# tweeq-MITO.net
KiCad netlist of a schematic drawn in EAGLE
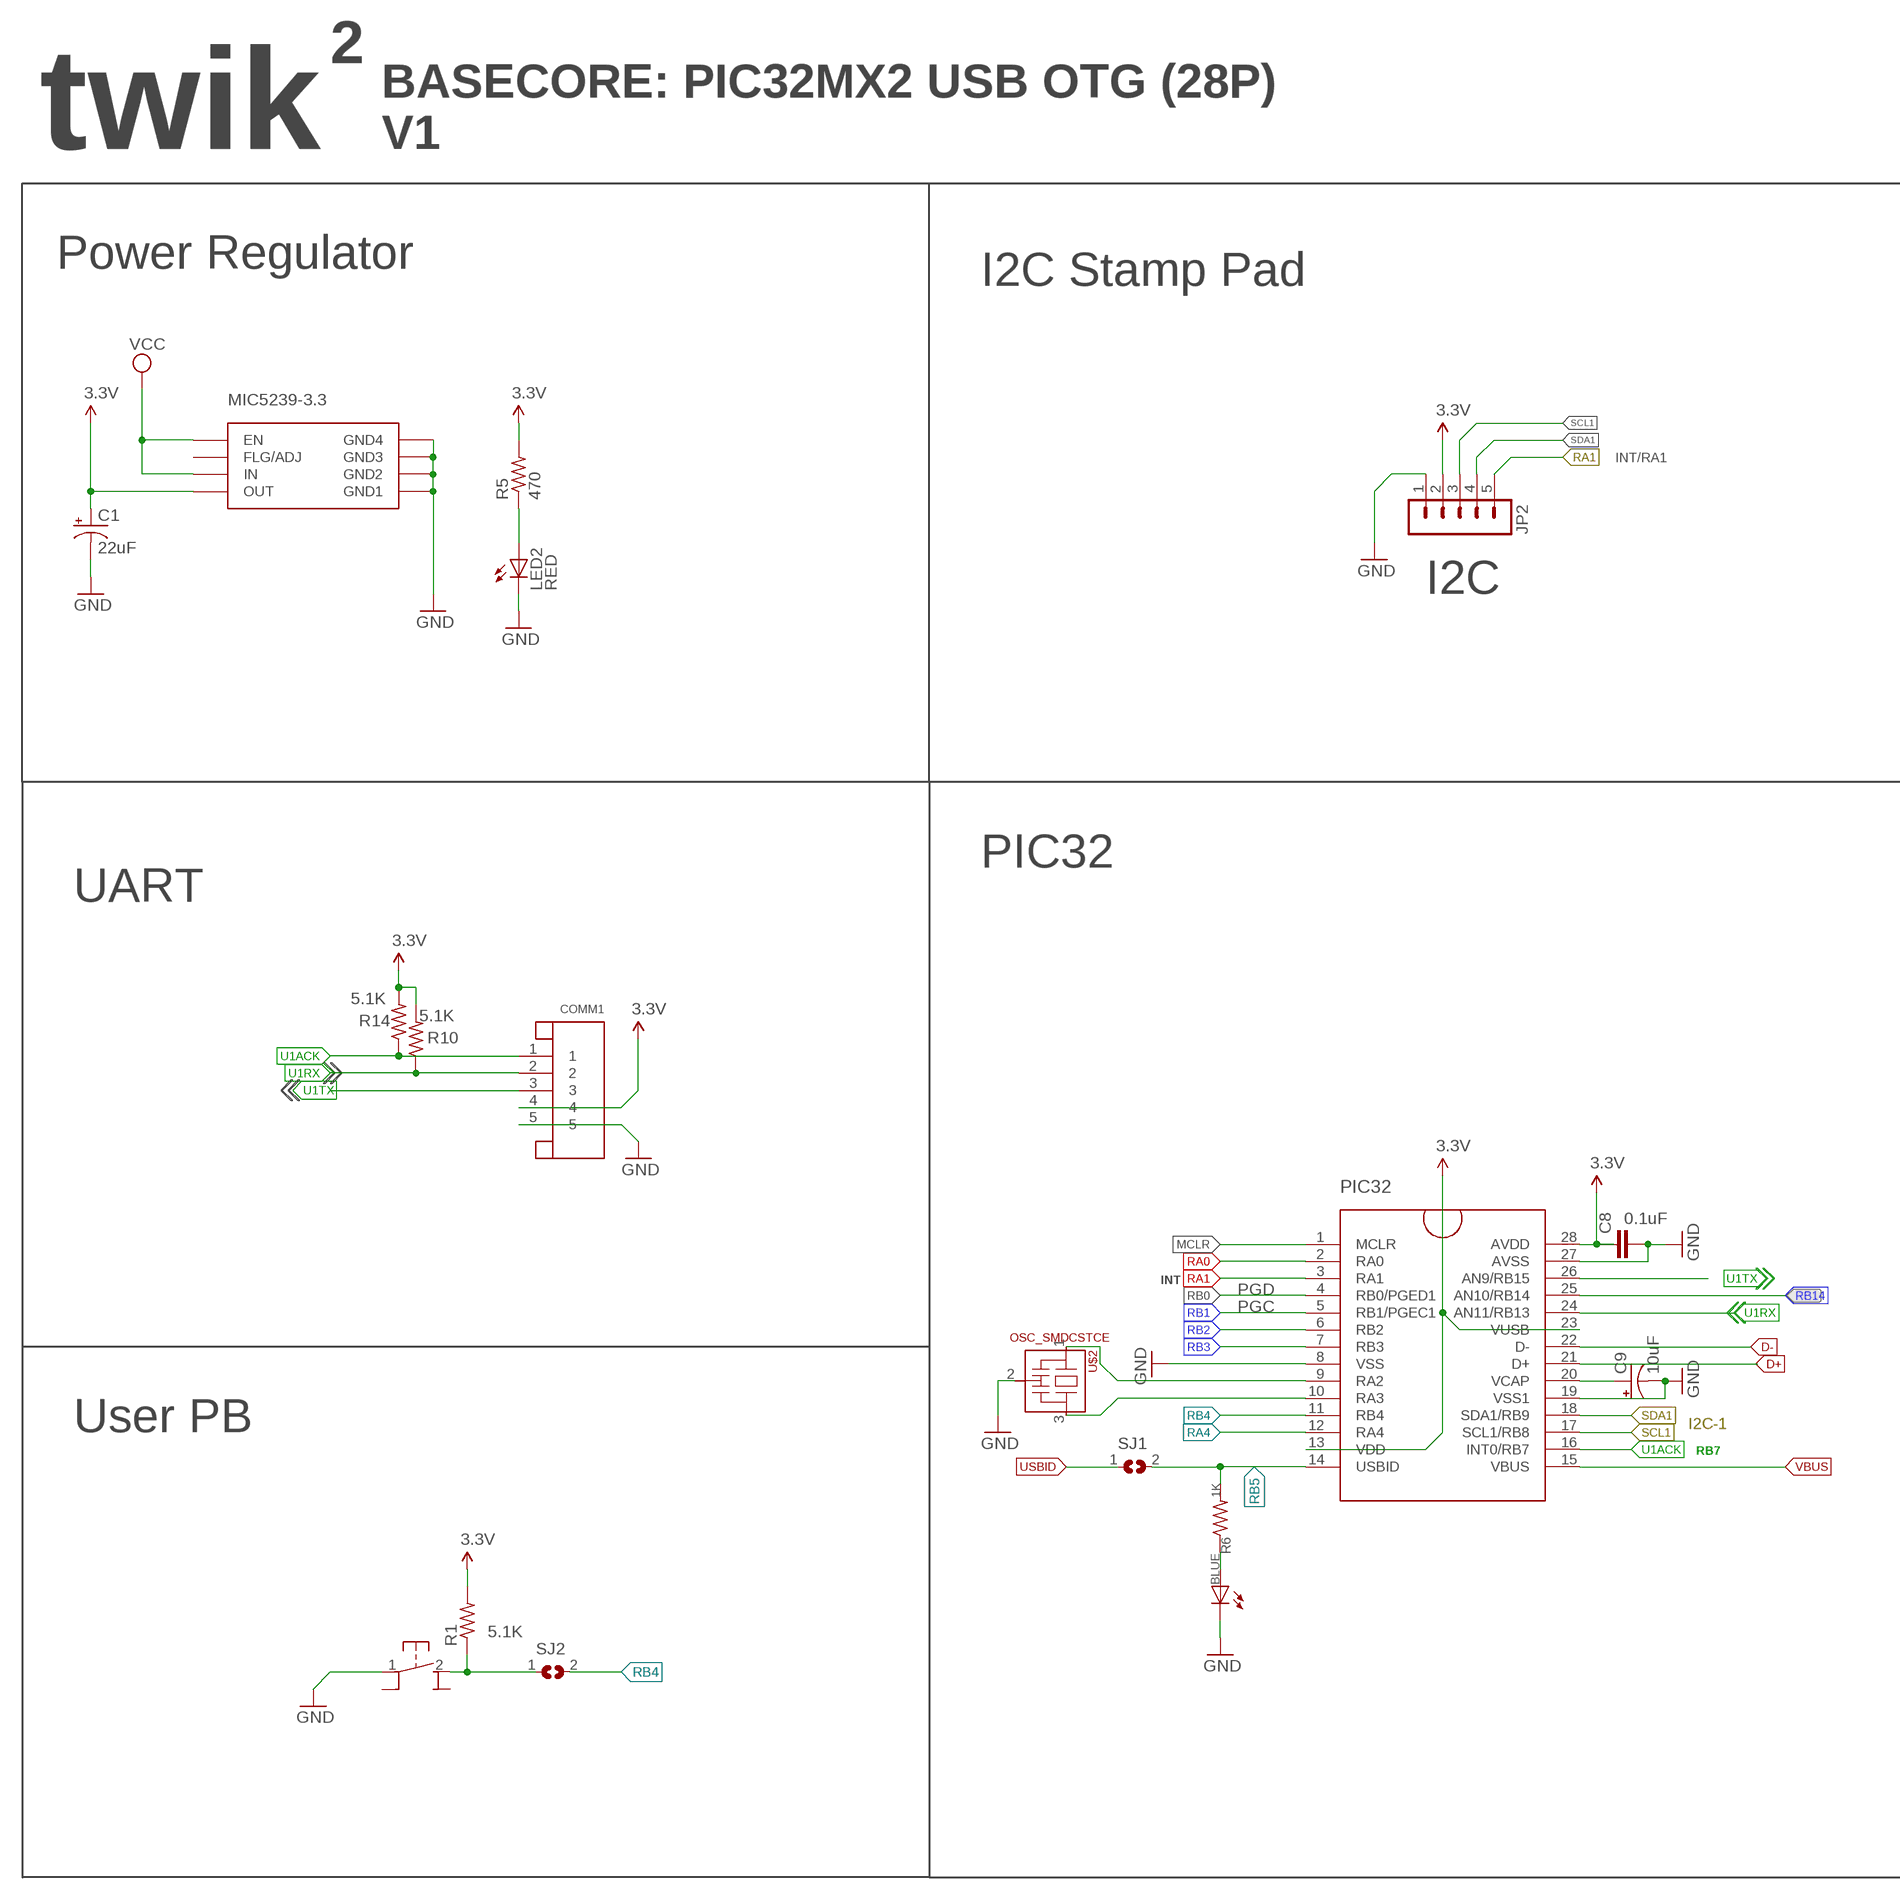
[diagram p0: schematic, sheet 1, part 1 of 2]
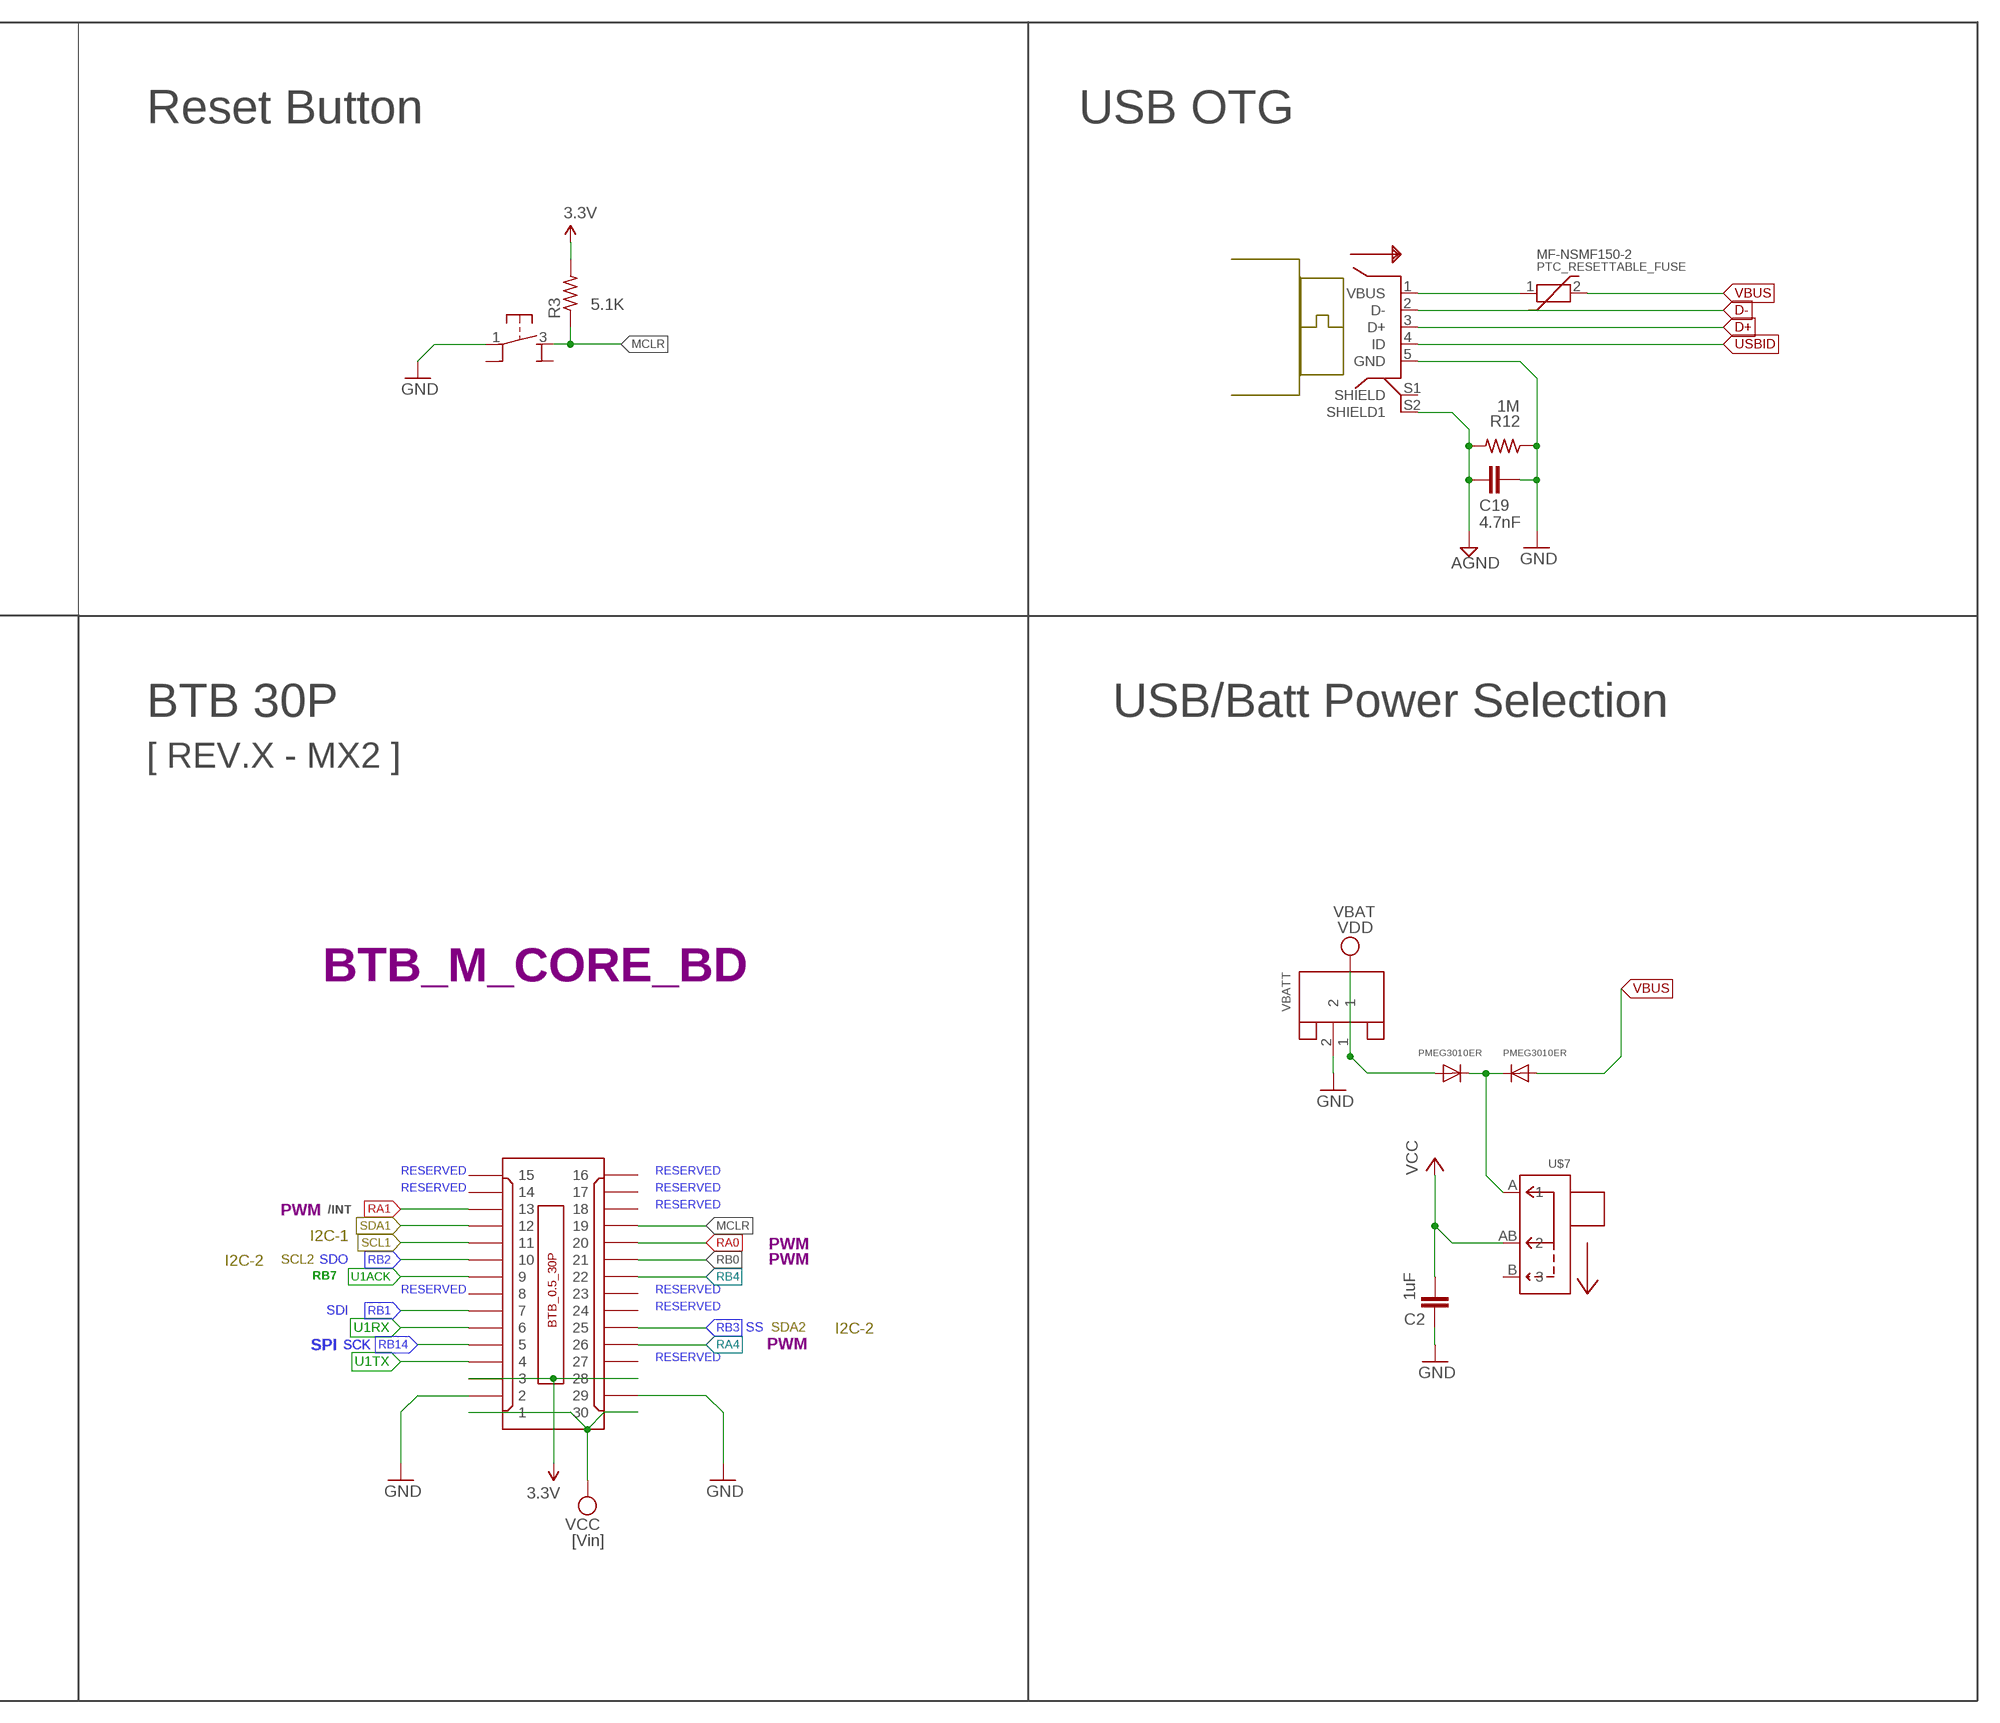
[diagram p1: schematic, sheet 1, part 2 of 2]

(export (version "E")
  (design (tool "Eeschema 10.0.6"))
  (components
    (comp (ref "C1")
      (value "22uF")
      (footprint "eagle-import:SMC_B")
      (libsource (lib "eagle-import") (part "CPOL-USSMCB"))
    )
    (comp (ref "C2")
      (value "1uF")
      (footprint "eagle-import:C0603K")
      (libsource (lib "eagle-import") (part "C-EUC0603K"))
    )
    (comp (ref "C8")
      (value "0.1uF")
      (footprint "eagle-import:C0402K")
      (libsource (lib "eagle-import") (part "C-EUC0402K"))
    )
    (comp (ref "C9")
      (value "10uF")
      (footprint "eagle-import:A_3216-18R")
      (libsource (lib "eagle-import") (part "CPOL-USA/3216-18R"))
    )
    (comp (ref "C19")
      (value "4.7nF")
      (footprint "eagle-import:C0402K")
      (libsource (lib "eagle-import") (part "C-EUC0402K"))
    )
    (comp (ref "COMM1")
      (value "JST-5PINSH")
      (footprint "eagle-import:SH1.0-5PIN")
      (libsource (lib "eagle-import") (part "JST-5PINSH"))
    )
    (comp (ref "JP2")
      (value "M05-11.5MM-SMT")
      (footprint "eagle-import:1X05-1.5MM-SMT")
      (libsource (lib "eagle-import") (part "M05-11.5MM-SMT"))
    )
    (comp (ref "LED2")
      (value "RED")
      (footprint "eagle-import:CHIP-LED0603")
      (libsource (lib "eagle-import") (part "LEDCHIP-LED0603"))
    )
    (comp (ref "MIC5239-3.3")
      (value "MIC5239-MM")
      (footprint "eagle-import:MSOP8")
      (libsource (lib "eagle-import") (part "MIC5239-MM"))
    )
    (comp (ref "PIC32")
      (value "PIC32MX2_B")
      (footprint "eagle-import:SSOP28")
      (libsource (lib "eagle-import") (part "PIC32MX2_B"))
    )
    (comp (ref "PIC_LED")
      (value "BLUE")
      (footprint "eagle-import:CHIP-LED0603")
      (libsource (lib "eagle-import") (part "LEDCHIP-LED0603"))
    )
    (comp (ref "PTC_RESETTABLE_FUSE")
      (value "PTC_FUSE/MF-NSMF150-2")
      (footprint "eagle-import:1206F")
      (libsource (lib "eagle-import") (part "PTC_FUSE/MF-NSMF150-2"))
    )
    (comp (ref "R1")
      (value "5.1K")
      (footprint "eagle-import:R0402")
      (libsource (lib "eagle-import") (part "R-US_R0402"))
    )
    (comp (ref "R3")
      (value "5.1K")
      (footprint "eagle-import:R0402")
      (libsource (lib "eagle-import") (part "R-US_R0402"))
    )
    (comp (ref "R5")
      (value "470")
      (footprint "eagle-import:R0402")
      (libsource (lib "eagle-import") (part "R-US_R0402"))
    )
    (comp (ref "R6")
      (value "1K")
      (footprint "eagle-import:R0402")
      (libsource (lib "eagle-import") (part "R-US_R0402"))
    )
    (comp (ref "R10")
      (value "5.1K")
      (footprint "eagle-import:R0402")
      (libsource (lib "eagle-import") (part "R-US_R0402"))
    )
    (comp (ref "R12")
      (value "1M")
      (footprint "eagle-import:R0402")
      (libsource (lib "eagle-import") (part "R-US_R0402"))
    )
    (comp (ref "R14")
      (value "5.1K")
      (footprint "eagle-import:R0402")
      (libsource (lib "eagle-import") (part "R-US_R0402"))
    )
    (comp (ref "SJ1")
      (value "JUMPER_SJ")
      (footprint "eagle-import:JUMPER_SJ")
      (libsource (lib "eagle-import") (part "JUMPER_SJ"))
    )
    (comp (ref "SJ2")
      (value "JUMPER_SJ")
      (footprint "eagle-import:JUMPER_SJ")
      (libsource (lib "eagle-import") (part "JUMPER_SJ"))
    )
    (comp (ref "U$1")
      (value "BTB_CONN_30P/M")
      (footprint "eagle-import:BTB0.5-30M-3.0G")
      (libsource (lib "eagle-import") (part "BTB_CONN_30P/M"))
    )
    (comp (ref "U$2")
      (value "OSC_SMDCSTCE")
      (footprint "eagle-import:CSTCE_RESONATOR_SMD")
      (libsource (lib "eagle-import") (part "OSC_SMDCSTCE"))
    )
    (comp (ref "U$3")
      (value "PB_MICRO_SMTRIGHTANGLE")
      (footprint "eagle-import:PB_SMT_90D6.2X4.6")
      (libsource (lib "eagle-import") (part "PB_MICRO_SMTRIGHTANGLE"))
    )
    (comp (ref "U$4")
      (value "PB_MICRO_SMT")
      (footprint "eagle-import:PB_SMT_3.5X3X2")
      (libsource (lib "eagle-import") (part "PB_MICRO_SMT"))
    )
    (comp (ref "U$7")
      (value "SLIDE_SWITCH_MINI/MSK1101")
      (footprint "eagle-import:MSK1101")
      (libsource (lib "eagle-import") (part "SLIDE_SWITCH_MINI/MSK1101"))
    )
    (comp (ref "U$9")
      (value "PMEG3010ER/MOD")
      (footprint "eagle-import:SOD123-MOD")
      (libsource (lib "eagle-import") (part "PMEG3010ER/MOD"))
    )
    (comp (ref "U$10")
      (value "PMEG3010ER/MOD")
      (footprint "eagle-import:SOD123-MOD")
      (libsource (lib "eagle-import") (part "PMEG3010ER/MOD"))
    )
    (comp (ref "U$12")
      (value "USB/MICRO-5PF-B")
      (footprint "eagle-import:MICRO_USB_5PF_B")
      (libsource (lib "eagle-import") (part "USB/MICRO-5PF-B"))
    )
    (comp (ref "VBATT")
      (value "JST-2PINSH")
      (footprint "eagle-import:SH1.0-2PIN")
      (libsource (lib "eagle-import") (part "JST-2PINSH"))
    )
  )
  (nets
    (net (code "1") (name "3.3V") (class "Default")
      (node (ref "C1") (pin "+") (pinfunction "+_+") (pintype "passive"))
      (node (ref "C8") (pin "1") (pinfunction "1_1") (pintype "passive"))
      (node (ref "COMM1") (pin "4") (pinfunction "4_4") (pintype "bidirectional"))
      (node (ref "JP2") (pin "2") (pinfunction "2_2") (pintype "passive"))
      (node (ref "MIC5239-3.3") (pin "4") (pinfunction "OUT_4") (pintype "bidirectional"))
      (node (ref "PIC32") (pin "13") (pinfunction "VDD_13") (pintype "bidirectional"))
      (node (ref "PIC32") (pin "23") (pinfunction "VUSB_23") (pintype "bidirectional"))
      (node (ref "PIC32") (pin "28") (pinfunction "AVDD_28") (pintype "bidirectional"))
      (node (ref "R1") (pin "2") (pinfunction "2_2") (pintype "passive"))
      (node (ref "R10") (pin "2") (pinfunction "2_2") (pintype "passive"))
      (node (ref "R14") (pin "2") (pinfunction "2_2") (pintype "passive"))
      (node (ref "R3") (pin "2") (pinfunction "2_2") (pintype "passive"))
      (node (ref "R5") (pin "2") (pinfunction "2_2") (pintype "passive"))
      (node (ref "U$1") (pin "28") (pinfunction "28_28") (pintype "bidirectional"))
      (node (ref "U$1") (pin "3") (pinfunction "3_3") (pintype "bidirectional"))
    )
    (net (code "2") (name "AGND") (class "Default")
      (node (ref "C19") (pin "2") (pinfunction "2_2") (pintype "passive"))
      (node (ref "R12") (pin "2") (pinfunction "2_2") (pintype "passive"))
      (node (ref "U$12") (pin "S2") (pinfunction "SHIELD1_S2") (pintype "bidirectional"))
    )
    (net (code "3") (name "D+") (class "Default")
      (node (ref "PIC32") (pin "21") (pinfunction "D+_21") (pintype "bidirectional"))
      (node (ref "U$12") (pin "3") (pinfunction "D+_3") (pintype "bidirectional"))
    )
    (net (code "4") (name "D-") (class "Default")
      (node (ref "PIC32") (pin "22") (pinfunction "D-_22") (pintype "bidirectional"))
      (node (ref "U$12") (pin "2") (pinfunction "D-_2") (pintype "bidirectional"))
    )
    (net (code "5") (name "GND") (class "Default")
      (node (ref "C1") (pin "-") (pinfunction "-_-") (pintype "passive"))
      (node (ref "C19") (pin "1") (pinfunction "1_1") (pintype "passive"))
      (node (ref "C2") (pin "1") (pinfunction "1_1") (pintype "passive"))
      (node (ref "C8") (pin "2") (pinfunction "2_2") (pintype "passive"))
      (node (ref "C9") (pin "-") (pinfunction "-_-") (pintype "passive"))
      (node (ref "COMM1") (pin "5") (pinfunction "5_5") (pintype "bidirectional"))
      (node (ref "JP2") (pin "1") (pinfunction "1_1") (pintype "passive"))
      (node (ref "LED2") (pin "C") (pinfunction "C_C") (pintype "passive"))
      (node (ref "MIC5239-3.3") (pin "5") (pinfunction "GND1_5") (pintype "bidirectional"))
      (node (ref "MIC5239-3.3") (pin "6") (pinfunction "GND2_6") (pintype "bidirectional"))
      (node (ref "MIC5239-3.3") (pin "7") (pinfunction "GND3_7") (pintype "bidirectional"))
      (node (ref "MIC5239-3.3") (pin "8") (pinfunction "GND4_8") (pintype "bidirectional"))
      (node (ref "PIC32") (pin "19") (pinfunction "VSS1_19") (pintype "bidirectional"))
      (node (ref "PIC32") (pin "27") (pinfunction "AVSS_27") (pintype "bidirectional"))
      (node (ref "PIC32") (pin "8") (pinfunction "VSS_8") (pintype "bidirectional"))
      (node (ref "PIC_LED") (pin "C") (pinfunction "C_C") (pintype "passive"))
      (node (ref "R12") (pin "1") (pinfunction "1_1") (pintype "passive"))
      (node (ref "U$1") (pin "2") (pinfunction "2_2") (pintype "bidirectional"))
      (node (ref "U$1") (pin "29") (pinfunction "29_29") (pintype "bidirectional"))
      (node (ref "U$12") (pin "5") (pinfunction "GND_5") (pintype "bidirectional"))
      (node (ref "U$2") (pin "2") (pinfunction "VSS_2") (pintype "power_in"))
      (node (ref "U$3") (pin "1") (pinfunction "1_1") (pintype "passive"))
      (node (ref "U$4") (pin "1") (pinfunction "1_1") (pintype "passive"))
      (node (ref "VBATT") (pin "2") (pinfunction "2_2") (pintype "bidirectional"))
    )
    (net (code "6") (name "MCLR") (class "Default")
      (node (ref "PIC32") (pin "1") (pinfunction "MCLR_1") (pintype "bidirectional"))
      (node (ref "R3") (pin "1") (pinfunction "1_1") (pintype "passive"))
      (node (ref "U$1") (pin "19") (pinfunction "19_19") (pintype "bidirectional"))
      (node (ref "U$4") (pin "3") (pinfunction "2_3") (pintype "passive"))
    )
    (net (code "7") (name "Net-(LED2-PadA)") (class "Default")
      (node (ref "LED2") (pin "A") (pinfunction "A_A") (pintype "passive"))
      (node (ref "R5") (pin "1") (pinfunction "1_1") (pintype "passive"))
    )
    (net (code "8") (name "Net-(PIC32-RA2)") (class "Default")
      (node (ref "PIC32") (pin "9") (pinfunction "RA2_9") (pintype "bidirectional"))
      (node (ref "U$2") (pin "1") (pinfunction "1_1") (pintype "output"))
    )
    (net (code "9") (name "Net-(PIC32-RA3)") (class "Default")
      (node (ref "PIC32") (pin "10") (pinfunction "RA3_10") (pintype "bidirectional"))
      (node (ref "U$2") (pin "3") (pinfunction "3_3") (pintype "input"))
    )
    (net (code "10") (name "Net-(PIC32-VCAP)") (class "Default")
      (node (ref "C9") (pin "+") (pinfunction "+_+") (pintype "passive"))
      (node (ref "PIC32") (pin "20") (pinfunction "VCAP_20") (pintype "bidirectional"))
    )
    (net (code "11") (name "Net-(PIC_LED-PadA)") (class "Default")
      (node (ref "PIC_LED") (pin "A") (pinfunction "A_A") (pintype "passive"))
      (node (ref "R6") (pin "1") (pinfunction "1_1") (pintype "passive"))
    )
    (net (code "12") (name "Net-(R1-Pad1)") (class "Default")
      (node (ref "R1") (pin "1") (pinfunction "1_1") (pintype "passive"))
      (node (ref "SJ2") (pin "1") (pinfunction "1_1") (pintype "passive"))
      (node (ref "U$3") (pin "2") (pinfunction "2_2") (pintype "passive"))
    )
    (net (code "13") (name "Net-(U$7-1)") (class "Default")
      (node (ref "U$10") (pin "C") (pinfunction "C_C") (pintype "passive"))
      (node (ref "U$7") (pin "A") (pinfunction "1_A") (pintype "bidirectional"))
      (node (ref "U$9") (pin "C") (pinfunction "C_C") (pintype "passive"))
    )
    (net (code "14") (name "Net-(U$12-VBUS)") (class "Default")
      (node (ref "PTC_RESETTABLE_FUSE") (pin "1") (pinfunction "1_1") (pintype "bidirectional"))
      (node (ref "U$12") (pin "1") (pinfunction "VBUS_1") (pintype "bidirectional"))
    )
    (net (code "15") (name "RA0") (class "Default")
      (node (ref "PIC32") (pin "2") (pinfunction "RA0_2") (pintype "bidirectional"))
      (node (ref "U$1") (pin "20") (pinfunction "20_20") (pintype "bidirectional"))
    )
    (net (code "16") (name "RA1") (class "Default")
      (node (ref "JP2") (pin "5") (pinfunction "5_5") (pintype "passive"))
      (node (ref "PIC32") (pin "3") (pinfunction "RA1_3") (pintype "bidirectional"))
      (node (ref "U$1") (pin "13") (pinfunction "13_13") (pintype "bidirectional"))
    )
    (net (code "17") (name "RA4") (class "Default")
      (node (ref "PIC32") (pin "12") (pinfunction "RA4_12") (pintype "bidirectional"))
      (node (ref "U$1") (pin "26") (pinfunction "26_26") (pintype "bidirectional"))
    )
    (net (code "18") (name "RB0") (class "Default")
      (node (ref "PIC32") (pin "4") (pinfunction "RB0/PGED1_4") (pintype "bidirectional"))
      (node (ref "U$1") (pin "21") (pinfunction "21_21") (pintype "bidirectional"))
    )
    (net (code "19") (name "RB1") (class "Default")
      (node (ref "PIC32") (pin "5") (pinfunction "RB1/PGEC1_5") (pintype "bidirectional"))
      (node (ref "U$1") (pin "7") (pinfunction "7_7") (pintype "bidirectional"))
    )
    (net (code "20") (name "RB2") (class "Default")
      (node (ref "PIC32") (pin "6") (pinfunction "RB2_6") (pintype "bidirectional"))
      (node (ref "U$1") (pin "10") (pinfunction "10_10") (pintype "bidirectional"))
    )
    (net (code "21") (name "RB3") (class "Default")
      (node (ref "PIC32") (pin "7") (pinfunction "RB3_7") (pintype "bidirectional"))
      (node (ref "U$1") (pin "25") (pinfunction "25_25") (pintype "bidirectional"))
    )
    (net (code "22") (name "RB4") (class "Default")
      (node (ref "PIC32") (pin "11") (pinfunction "RB4_11") (pintype "bidirectional"))
      (node (ref "SJ2") (pin "2") (pinfunction "2_2") (pintype "passive"))
      (node (ref "U$1") (pin "22") (pinfunction "22_22") (pintype "bidirectional"))
    )
    (net (code "23") (name "RB5") (class "Default")
      (node (ref "PIC32") (pin "14") (pinfunction "USBID_14") (pintype "bidirectional"))
      (node (ref "R6") (pin "2") (pinfunction "2_2") (pintype "passive"))
      (node (ref "SJ1") (pin "2") (pinfunction "2_2") (pintype "passive"))
    )
    (net (code "24") (name "RB14") (class "Default")
      (node (ref "PIC32") (pin "25") (pinfunction "AN10/RB14_25") (pintype "bidirectional"))
      (node (ref "U$1") (pin "5") (pinfunction "5_5") (pintype "bidirectional"))
    )
    (net (code "25") (name "SCL1") (class "Default")
      (node (ref "JP2") (pin "3") (pinfunction "3_3") (pintype "passive"))
      (node (ref "PIC32") (pin "17") (pinfunction "SCL1/RB8_17") (pintype "bidirectional"))
      (node (ref "U$1") (pin "11") (pinfunction "11_11") (pintype "bidirectional"))
    )
    (net (code "26") (name "SDA1") (class "Default")
      (node (ref "JP2") (pin "4") (pinfunction "4_4") (pintype "passive"))
      (node (ref "PIC32") (pin "18") (pinfunction "SDA1/RB9_18") (pintype "bidirectional"))
      (node (ref "U$1") (pin "12") (pinfunction "12_12") (pintype "bidirectional"))
    )
    (net (code "27") (name "U1ACK") (class "Default")
      (node (ref "COMM1") (pin "1") (pinfunction "1_1") (pintype "bidirectional"))
      (node (ref "PIC32") (pin "16") (pinfunction "INT0/RB7_16") (pintype "bidirectional"))
      (node (ref "R14") (pin "1") (pinfunction "1_1") (pintype "passive"))
      (node (ref "U$1") (pin "9") (pinfunction "9_9") (pintype "bidirectional"))
    )
    (net (code "28") (name "U1RX") (class "Default")
      (node (ref "COMM1") (pin "2") (pinfunction "2_2") (pintype "bidirectional"))
      (node (ref "PIC32") (pin "24") (pinfunction "AN11/RB13_24") (pintype "bidirectional"))
      (node (ref "R10") (pin "1") (pinfunction "1_1") (pintype "passive"))
      (node (ref "U$1") (pin "6") (pinfunction "6_6") (pintype "bidirectional"))
    )
    (net (code "29") (name "U1TX") (class "Default")
      (node (ref "COMM1") (pin "3") (pinfunction "3_3") (pintype "bidirectional"))
      (node (ref "PIC32") (pin "26") (pinfunction "AN9/RB15_26") (pintype "bidirectional"))
      (node (ref "U$1") (pin "4") (pinfunction "4_4") (pintype "bidirectional"))
    )
    (net (code "30") (name "USBID") (class "Default")
      (node (ref "SJ1") (pin "1") (pinfunction "1_1") (pintype "passive"))
      (node (ref "U$12") (pin "4") (pinfunction "ID_4") (pintype "bidirectional"))
    )
    (net (code "31") (name "VBUS") (class "Default")
      (node (ref "PIC32") (pin "15") (pinfunction "VBUS_15") (pintype "bidirectional"))
      (node (ref "PTC_RESETTABLE_FUSE") (pin "2") (pinfunction "2_2") (pintype "bidirectional"))
      (node (ref "U$10") (pin "A") (pinfunction "A_A") (pintype "passive"))
    )
    (net (code "32") (name "VCC") (class "Default")
      (node (ref "C2") (pin "2") (pinfunction "2_2") (pintype "passive"))
      (node (ref "MIC5239-3.3") (pin "1") (pinfunction "EN_1") (pintype "bidirectional"))
      (node (ref "MIC5239-3.3") (pin "3") (pinfunction "IN_3") (pintype "bidirectional"))
      (node (ref "U$1") (pin "1") (pinfunction "1_1") (pintype "bidirectional"))
      (node (ref "U$1") (pin "30") (pinfunction "30_30") (pintype "bidirectional"))
      (node (ref "U$7") (pin "AB") (pinfunction "2_AB") (pintype "bidirectional"))
    )
    (net (code "33") (name "VDD") (class "Default")
      (node (ref "U$9") (pin "A") (pinfunction "A_A") (pintype "passive"))
      (node (ref "VBATT") (pin "1") (pinfunction "1_1") (pintype "bidirectional"))
    )
    (net (code "34") (name "unconnected-(MIC5239-3.3-FLG{slash}ADJ-Pad2)") (class "Default")
      (node (ref "MIC5239-3.3") (pin "2") (pinfunction "FLG/ADJ_2") (pintype "bidirectional"))
    )
    (net (code "35") (name "unconnected-(U$1-Pad8)") (class "Default")
      (node (ref "U$1") (pin "8") (pinfunction "8_8") (pintype "bidirectional"))
    )
    (net (code "36") (name "unconnected-(U$1-Pad14)") (class "Default")
      (node (ref "U$1") (pin "14") (pinfunction "14_14") (pintype "bidirectional"))
    )
    (net (code "37") (name "unconnected-(U$1-Pad15)") (class "Default")
      (node (ref "U$1") (pin "15") (pinfunction "15_15") (pintype "bidirectional"))
    )
    (net (code "38") (name "unconnected-(U$1-Pad16)") (class "Default")
      (node (ref "U$1") (pin "16") (pinfunction "16_16") (pintype "bidirectional"))
    )
    (net (code "39") (name "unconnected-(U$1-Pad17)") (class "Default")
      (node (ref "U$1") (pin "17") (pinfunction "17_17") (pintype "bidirectional"))
    )
    (net (code "40") (name "unconnected-(U$1-Pad18)") (class "Default")
      (node (ref "U$1") (pin "18") (pinfunction "18_18") (pintype "bidirectional"))
    )
    (net (code "41") (name "unconnected-(U$1-Pad23)") (class "Default")
      (node (ref "U$1") (pin "23") (pinfunction "23_23") (pintype "bidirectional"))
    )
    (net (code "42") (name "unconnected-(U$1-Pad24)") (class "Default")
      (node (ref "U$1") (pin "24") (pinfunction "24_24") (pintype "bidirectional"))
    )
    (net (code "43") (name "unconnected-(U$1-Pad27)") (class "Default")
      (node (ref "U$1") (pin "27") (pinfunction "27_27") (pintype "bidirectional"))
    )
    (net (code "44") (name "unconnected-(U$3-Pad1A)") (class "Default")
      (node (ref "U$3") (pin "1A") (pinfunction "1A_1A") (pintype "passive"))
    )
    (net (code "45") (name "unconnected-(U$3-Pad2A)") (class "Default")
      (node (ref "U$3") (pin "2A") (pinfunction "2A_2A") (pintype "passive"))
    )
    (net (code "46") (name "unconnected-(U$4-1A-Pad2)") (class "Default")
      (node (ref "U$4") (pin "2") (pinfunction "1A_2") (pintype "passive"))
    )
    (net (code "47") (name "unconnected-(U$4-2A-Pad4)") (class "Default")
      (node (ref "U$4") (pin "4") (pinfunction "2A_4") (pintype "passive"))
    )
    (net (code "48") (name "unconnected-(U$7-3-PadB)") (class "Default")
      (node (ref "U$7") (pin "B") (pinfunction "3_B") (pintype "bidirectional"))
    )
    (net (code "49") (name "unconnected-(U$12-SHIELD-PadS1)") (class "Default")
      (node (ref "U$12") (pin "S1") (pinfunction "SHIELD_S1") (pintype "bidirectional"))
    )
  )
)
